# halfbridge.net
KiCad netlist of a schematic drawn in Altium Designer
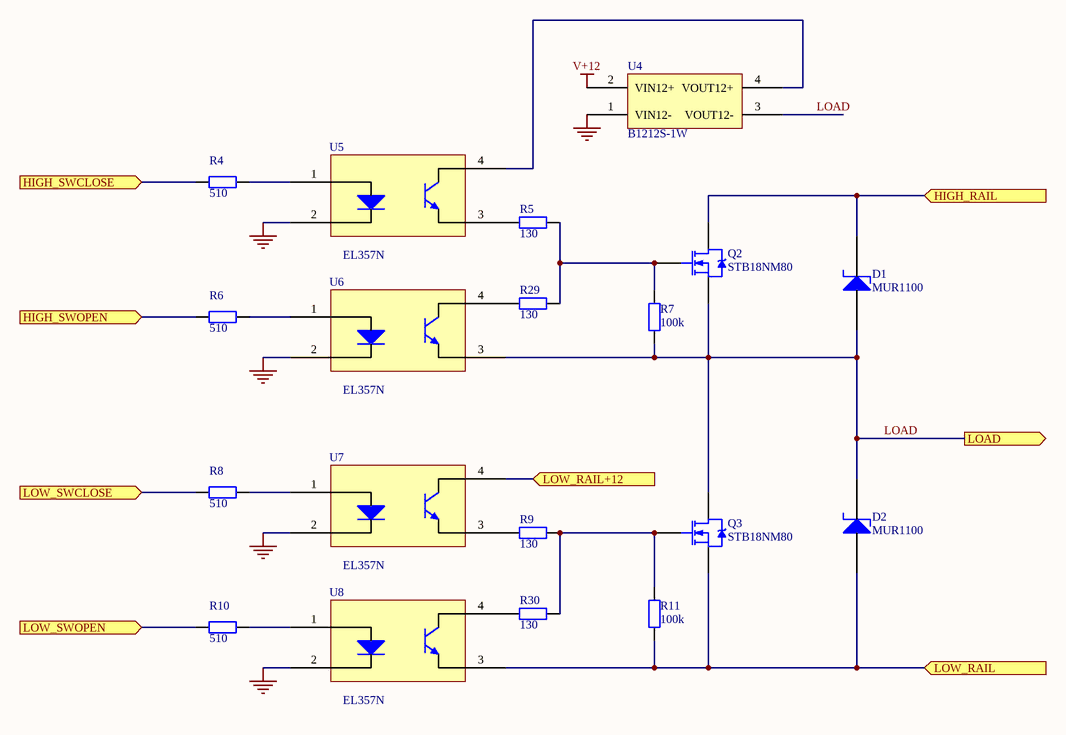
[diagram p0: halfbridge.SchDoc]

(export (version "E")
  (design (tool "Eeschema 10.0.6"))
  (components
    (comp (ref "D1")
      (value "MUR1100")
      (footprint "DIODE-0.4")
      (libsource (lib "components") (part "MUR1100"))
    )
    (comp (ref "D2")
      (value "MUR1100")
      (footprint "DIODE-0.4")
      (libsource (lib "components") (part "MUR1100"))
    )
    (comp (ref "Q2")
      (value "STB18NM80")
      (footprint "STB18NM80")
      (libsource (lib "components") (part "STB18NM80"))
    )
    (comp (ref "Q3")
      (value "STB18NM80")
      (footprint "STB18NM80")
      (libsource (lib "components") (part "STB18NM80"))
    )
    (comp (ref "R4")
      (value "510")
      (footprint "RESC1608L")
      (description "Resistor")
      (fields (field (name "PUBLISHER") "Altium Limited"))
      (libsource (lib "*") (part "Res2"))
    )
    (comp (ref "R5")
      (value "130")
      (footprint "RESC1608L")
      (description "Resistor")
      (fields (field (name "PUBLISHER") "Altium Limited"))
      (libsource (lib "*") (part "Res2"))
    )
    (comp (ref "R6")
      (value "510")
      (footprint "RESC1608L")
      (description "Resistor")
      (fields (field (name "PUBLISHER") "Altium Limited"))
      (libsource (lib "*") (part "Res2"))
    )
    (comp (ref "R7")
      (value "100k")
      (footprint "RESC1608L")
      (description "Resistor")
      (fields (field (name "PUBLISHER") "Altium Limited"))
      (libsource (lib "") (part "Res2_1"))
    )
    (comp (ref "R8")
      (value "510")
      (footprint "RESC1608L")
      (description "Resistor")
      (fields (field (name "PUBLISHER") "Altium Limited"))
      (libsource (lib "*") (part "Res2"))
    )
    (comp (ref "R9")
      (value "130")
      (footprint "RESC1608L")
      (description "Resistor")
      (fields (field (name "PUBLISHER") "Altium Limited"))
      (libsource (lib "*") (part "Res2"))
    )
    (comp (ref "R10")
      (value "510")
      (footprint "RESC1608L")
      (description "Resistor")
      (fields (field (name "PUBLISHER") "Altium Limited"))
      (libsource (lib "*") (part "Res2"))
    )
    (comp (ref "R11")
      (value "100k")
      (footprint "RESC1608L")
      (description "Resistor")
      (fields (field (name "PUBLISHER") "Altium Limited"))
      (libsource (lib "") (part "Res2_1"))
    )
    (comp (ref "R29")
      (value "130")
      (footprint "RESC1608L")
      (description "Resistor")
      (fields (field (name "PUBLISHER") "Altium Limited"))
      (libsource (lib "*") (part "Res2"))
    )
    (comp (ref "R30")
      (value "130")
      (footprint "RESC1608L")
      (description "Resistor")
      (fields (field (name "PUBLISHER") "Altium Limited"))
      (libsource (lib "*") (part "Res2"))
    )
    (comp (ref "U4")
      (value "B1212S-1W")
      (footprint "B1212S-1W")
      (libsource (lib "components") (part "B1212S-1W"))
    )
    (comp (ref "U5") (value "EL357N") (footprint "EL357N") (libsource (lib "components") (part "EL357N")))
    (comp (ref "U6") (value "EL357N") (footprint "EL357N") (libsource (lib "components") (part "EL357N")))
    (comp (ref "U7") (value "EL357N") (footprint "EL357N") (libsource (lib "components") (part "EL357N")))
    (comp (ref "U8") (value "EL357N") (footprint "EL357N") (libsource (lib "components") (part "EL357N")))
  )
  (nets
    (net (code "1") (name "/HIGH_RAIL") (class "Default")
      (node (ref "D1") (pin "2") (pinfunction "2_2") (pintype "passive"))
      (node (ref "Q2") (pin "2") (pinfunction "D_2") (pintype "passive"))
    )
    (net (code "2") (name "/HIGH_SWCLOSE") (class "Default")
      (node (ref "R4") (pin "1") (pinfunction "1_1") (pintype "passive"))
    )
    (net (code "3") (name "/HIGH_SWOPEN") (class "Default")
      (node (ref "R6") (pin "1") (pinfunction "1_1") (pintype "passive"))
    )
    (net (code "4") (name "/LOAD") (class "Default")
      (node (ref "D1") (pin "1") (pinfunction "1_1") (pintype "passive"))
      (node (ref "D2") (pin "2") (pinfunction "2_2") (pintype "passive"))
      (node (ref "Q2") (pin "3") (pinfunction "S_3") (pintype "passive"))
      (node (ref "Q3") (pin "2") (pinfunction "D_2") (pintype "passive"))
      (node (ref "R7") (pin "1") (pinfunction "1_1") (pintype "passive"))
      (node (ref "U4") (pin "3") (pinfunction "VOUT12-_3") (pintype "passive"))
      (node (ref "U6") (pin "3") (pinfunction "Emitter_3") (pintype "passive"))
    )
    (net (code "5") (name "/LOW_RAIL") (class "Default")
      (node (ref "D2") (pin "1") (pinfunction "1_1") (pintype "passive"))
      (node (ref "Q3") (pin "3") (pinfunction "S_3") (pintype "passive"))
      (node (ref "R11") (pin "1") (pinfunction "1_1") (pintype "passive"))
      (node (ref "U8") (pin "3") (pinfunction "Emitter_3") (pintype "passive"))
    )
    (net (code "6") (name "/LOW_RAIL+12") (class "Default")
      (node (ref "U7") (pin "4") (pinfunction "Collector_4") (pintype "passive"))
    )
    (net (code "7") (name "/LOW_SWCLOSE") (class "Default")
      (node (ref "R8") (pin "1") (pinfunction "1_1") (pintype "passive"))
    )
    (net (code "8") (name "/LOW_SWOPEN") (class "Default")
      (node (ref "R10") (pin "1") (pinfunction "1_1") (pintype "passive"))
    )
    (net (code "9") (name "GND") (class "Default")
      (node (ref "U4") (pin "1") (pinfunction "VIN12-_1") (pintype "passive"))
      (node (ref "U5") (pin "2") (pinfunction "Cathode_2") (pintype "passive"))
      (node (ref "U6") (pin "2") (pinfunction "Cathode_2") (pintype "passive"))
      (node (ref "U7") (pin "2") (pinfunction "Cathode_2") (pintype "passive"))
      (node (ref "U8") (pin "2") (pinfunction "Cathode_2") (pintype "passive"))
    )
    (net (code "10") (name "Net-(Q2-G)") (class "Default")
      (node (ref "Q2") (pin "1") (pinfunction "G_1") (pintype "passive"))
      (node (ref "R29") (pin "2") (pinfunction "2_2") (pintype "passive"))
      (node (ref "R5") (pin "2") (pinfunction "2_2") (pintype "passive"))
      (node (ref "R7") (pin "2") (pinfunction "2_2") (pintype "passive"))
    )
    (net (code "11") (name "Net-(Q3-G)") (class "Default")
      (node (ref "Q3") (pin "1") (pinfunction "G_1") (pintype "passive"))
      (node (ref "R11") (pin "2") (pinfunction "2_2") (pintype "passive"))
      (node (ref "R30") (pin "2") (pinfunction "2_2") (pintype "passive"))
      (node (ref "R9") (pin "2") (pinfunction "2_2") (pintype "passive"))
    )
    (net (code "12") (name "Net-(U4-VOUT12+)") (class "Default")
      (node (ref "U4") (pin "4") (pinfunction "VOUT12+_4") (pintype "passive"))
      (node (ref "U5") (pin "4") (pinfunction "Collector_4") (pintype "passive"))
    )
    (net (code "13") (name "Net-(U5-Anode)") (class "Default")
      (node (ref "R4") (pin "2") (pinfunction "2_2") (pintype "passive"))
      (node (ref "U5") (pin "1") (pinfunction "Anode_1") (pintype "passive"))
    )
    (net (code "14") (name "Net-(U5-Emitter)") (class "Default")
      (node (ref "R5") (pin "1") (pinfunction "1_1") (pintype "passive"))
      (node (ref "U5") (pin "3") (pinfunction "Emitter_3") (pintype "passive"))
    )
    (net (code "15") (name "Net-(U6-Anode)") (class "Default")
      (node (ref "R6") (pin "2") (pinfunction "2_2") (pintype "passive"))
      (node (ref "U6") (pin "1") (pinfunction "Anode_1") (pintype "passive"))
    )
    (net (code "16") (name "Net-(U6-Collector)") (class "Default")
      (node (ref "R29") (pin "1") (pinfunction "1_1") (pintype "passive"))
      (node (ref "U6") (pin "4") (pinfunction "Collector_4") (pintype "passive"))
    )
    (net (code "17") (name "Net-(U7-Anode)") (class "Default")
      (node (ref "R8") (pin "2") (pinfunction "2_2") (pintype "passive"))
      (node (ref "U7") (pin "1") (pinfunction "Anode_1") (pintype "passive"))
    )
    (net (code "18") (name "Net-(U7-Emitter)") (class "Default")
      (node (ref "R9") (pin "1") (pinfunction "1_1") (pintype "passive"))
      (node (ref "U7") (pin "3") (pinfunction "Emitter_3") (pintype "passive"))
    )
    (net (code "19") (name "Net-(U8-Anode)") (class "Default")
      (node (ref "R10") (pin "2") (pinfunction "2_2") (pintype "passive"))
      (node (ref "U8") (pin "1") (pinfunction "Anode_1") (pintype "passive"))
    )
    (net (code "20") (name "Net-(U8-Collector)") (class "Default")
      (node (ref "R30") (pin "1") (pinfunction "1_1") (pintype "passive"))
      (node (ref "U8") (pin "4") (pinfunction "Collector_4") (pintype "passive"))
    )
    (net (code "21") (name "V+12") (class "Default")
      (node (ref "U4") (pin "2") (pinfunction "VIN12+_2") (pintype "passive"))
    )
  )
)
